# SMP_ASCII.net
KiCad netlist of a schematic drawn in Altium Designer
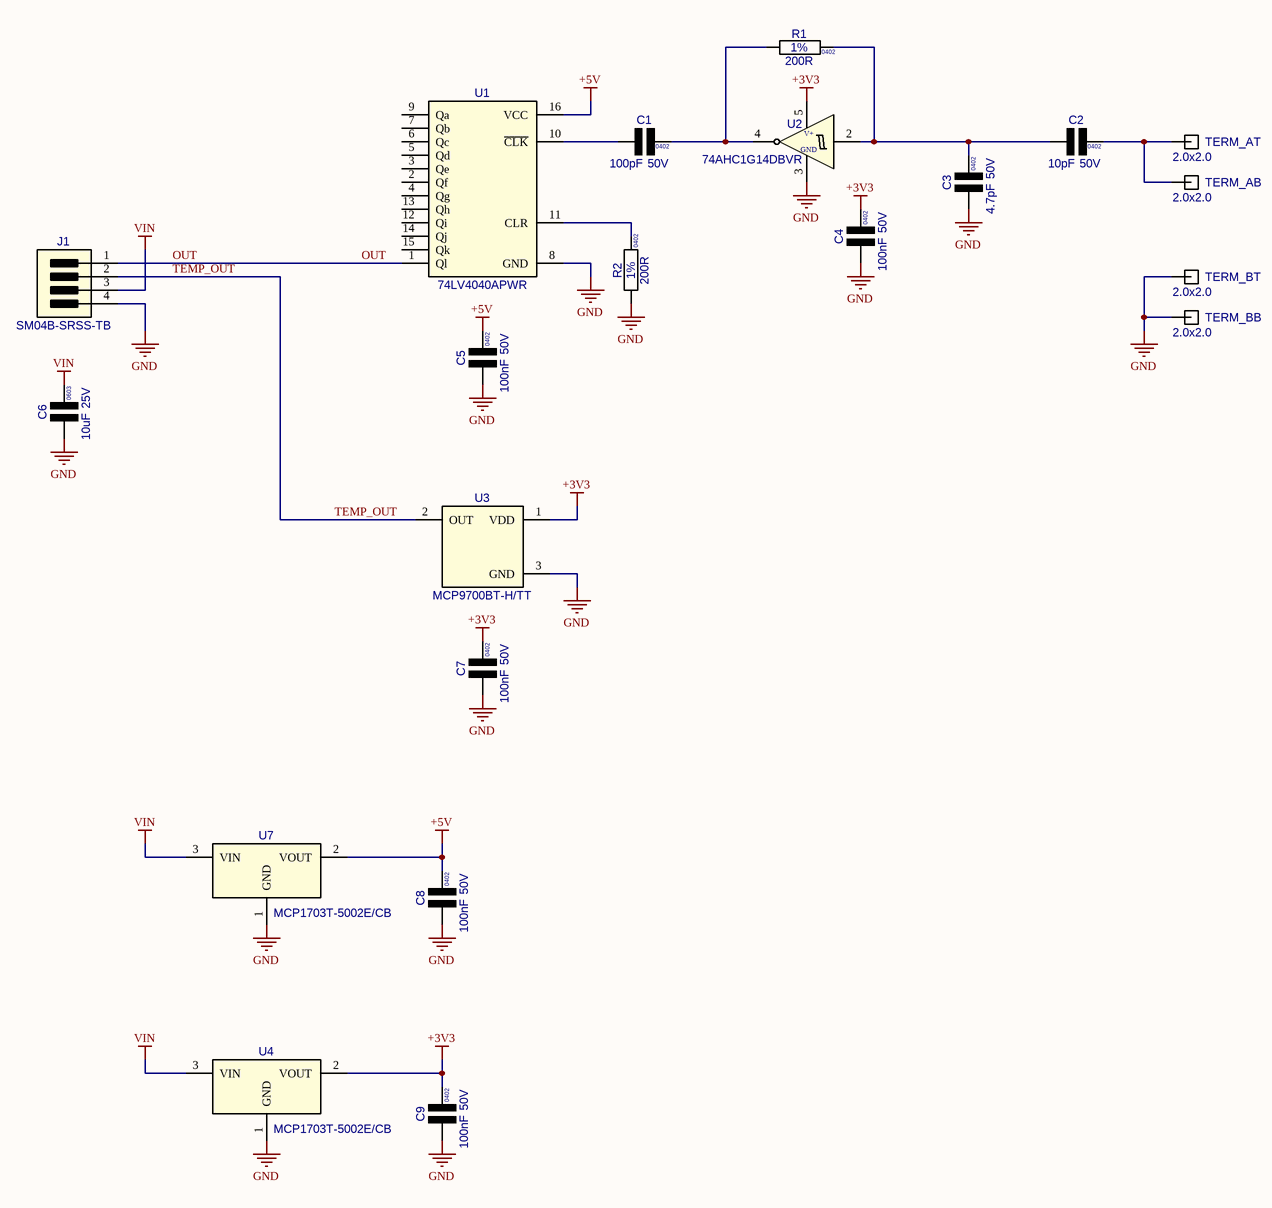
[diagram p0: SMP ASCII.SchDoc]

(export (version "E")
  (design (tool "Eeschema 10.0.6"))
  (components
    (comp (ref "C1")
      (value "100pF")
      (footprint "CAPC0402X60N")
      (description "Cap Ceramic C0G/NP0")
      (fields
        (field (name "MANUFACTURER") "Various")
        (field (name "PART NUMBER") "100pF 0402 50V 10% C0G/NP0")
        (field (name "VOLTAGE") "50V")
        (field (name "TEXT1") "0402")
      )
      (libsource (lib "Cap-Cer-SMD_V2") (part "100pF_0402N_50V_10%_C0G/NP0"))
    )
    (comp (ref "C2")
      (value "10pF")
      (footprint "CAPC0402X60N")
      (description "Cap Ceramic C0G/NP0")
      (fields
        (field (name "MANUFACTURER") "Various")
        (field (name "PART NUMBER") "10pF 0402 50V 5% C0G/NP0")
        (field (name "VOLTAGE") "50V")
        (field (name "TEXT1") "0402")
      )
      (libsource (lib "Cap-Cer-SMD_V2") (part "10pF_0402N_50V_5%_C0G/NP0"))
    )
    (comp (ref "C3")
      (value "4.7pF")
      (footprint "CAPC0402X60N")
      (description "Cap Ceramic C0G/NP0")
      (fields
        (field (name "MANUFACTURER") "Various")
        (field (name "PART NUMBER") "4.7pF 0402 50V 5% C0G/NP0")
        (field (name "VOLTAGE") "50V")
        (field (name "TEXT1") "0402")
      )
      (libsource (lib "Cap-Cer-SMD_V2") (part "4.7pF_0402N_50V_5%_C0G/NP0"))
    )
    (comp (ref "C4")
      (value "100nF")
      (footprint "CAPC0402X60N")
      (description "Cap Ceramic X5R")
      (fields
        (field (name "MANUFACTURER") "Various")
        (field (name "PART NUMBER") "100nF 0402 50V 5% X5R")
        (field (name "VOLTAGE") "50V")
        (field (name "TEXT1") "0402")
      )
      (libsource (lib "Cap-Cer-SMD_V2") (part "100nF_0402N_50V_5%_X5R"))
    )
    (comp (ref "C5")
      (value "100nF")
      (footprint "CAPC0402X60N")
      (description "Cap Ceramic X5R")
      (fields
        (field (name "MANUFACTURER") "Various")
        (field (name "PART NUMBER") "100nF 0402 50V 5% X5R")
        (field (name "VOLTAGE") "50V")
        (field (name "TEXT1") "0402")
      )
      (libsource (lib "Cap-Cer-SMD_V2") (part "100nF_0402N_50V_5%_X5R"))
    )
    (comp (ref "C6")
      (value "10uF")
      (footprint "CAPC0603X85N")
      (description "Cap Ceramic X5R")
      (fields
        (field (name "MANUFACTURER") "Various")
        (field (name "PART NUMBER") "10uF 0603 25V 10% X5R")
        (field (name "VOLTAGE") "25V")
        (field (name "TEXT1") "0603")
      )
      (libsource (lib "Cap-Cer-SMD_V2") (part "10uF_0603N_25V_10%_X5R"))
    )
    (comp (ref "C7")
      (value "100nF")
      (footprint "CAPC0402X60N")
      (description "Cap Ceramic X5R")
      (fields
        (field (name "MANUFACTURER") "Various")
        (field (name "PART NUMBER") "100nF 0402 50V 5% X5R")
        (field (name "VOLTAGE") "50V")
        (field (name "TEXT1") "0402")
      )
      (libsource (lib "Cap-Cer-SMD_V2") (part "100nF_0402N_50V_5%_X5R"))
    )
    (comp (ref "C8")
      (value "100nF")
      (footprint "CAPC0402X60N")
      (description "Cap Ceramic X5R")
      (fields
        (field (name "MANUFACTURER") "Various")
        (field (name "PART NUMBER") "100nF 0402 50V 5% X5R")
        (field (name "VOLTAGE") "50V")
        (field (name "TEXT1") "0402")
      )
      (libsource (lib "Cap-Cer-SMD_V2") (part "100nF_0402N_50V_5%_X5R"))
    )
    (comp (ref "C9")
      (value "100nF")
      (footprint "CAPC0402X60N")
      (description "Cap Ceramic X5R")
      (fields
        (field (name "MANUFACTURER") "Various")
        (field (name "PART NUMBER") "100nF 0402 50V 5% X5R")
        (field (name "VOLTAGE") "50V")
        (field (name "TEXT1") "0402")
      )
      (libsource (lib "Cap-Cer-SMD_V2") (part "100nF_0402N_50V_5%_X5R"))
    )
    (comp (ref "J1")
      (value "SM04B-SRSS-TB")
      (footprint "SM04B-SRSS-TB")
      (description "Connector Wire to Board 1.0mm Rt Angle")
      (fields (field (name "MANUFACTURER") "JST"))
      (libsource (lib "Connector-WtB") (part "SM04B-SRSS-TB"))
    )
    (comp (ref "R1")
      (value "200R")
      (footprint "RESC0402X40N")
      (description "Resistor Chip SMD")
      (fields
        (field (name "MANUFACTURER") "Various")
        (field (name "PART NUMBER") "200R 0402 1%")
        (field (name "TOL") "1%")
        (field (name "TEXT1") "0402")
      )
      (libsource (lib "Res-SMD_V2") (part "200R_0402"))
    )
    (comp (ref "R2")
      (value "200R")
      (footprint "RESC0402X40N")
      (description "Resistor Chip SMD")
      (fields
        (field (name "MANUFACTURER") "Various")
        (field (name "PART NUMBER") "200R 0402 1%")
        (field (name "TOL") "1%")
        (field (name "TEXT1") "0402")
      )
      (libsource (lib "Res-SMD_V2") (part "200R_0402"))
    )
    (comp (ref "TERM_AB")
      (value "Pad-SMD-2.0x2.0mm-H_Rectangle")
      (footprint "PAD-SMD-2.0x2.0mm Rect")
      (description "Surface Mount Pad 2.0x2.0mm Rectangle")
      (fields (field (name "MANUFACTURER") "NA") (field (name "PART NUMBER") "2.0x2.0"))
      (libsource (lib "Mechanical_V2") (part "Pad-SMD-2.0x2.0mm_Rectangle"))
    )
    (comp (ref "TERM_AT")
      (value "Pad-SMD-2.0x2.0mm-H_Rectangle")
      (footprint "PAD-SMD-2.0x2.0mm Rect")
      (description "Surface Mount Pad 2.0x2.0mm Rectangle")
      (fields (field (name "MANUFACTURER") "NA") (field (name "PART NUMBER") "2.0x2.0"))
      (libsource (lib "Mechanical_V2") (part "Pad-SMD-2.0x2.0mm_Rectangle"))
    )
    (comp (ref "TERM_BB")
      (value "Pad-SMD-2.0x2.0mm-H_Rectangle")
      (footprint "PAD-SMD-2.0x2.0mm Rect")
      (description "Surface Mount Pad 2.0x2.0mm Rectangle")
      (fields (field (name "MANUFACTURER") "NA") (field (name "PART NUMBER") "2.0x2.0"))
      (libsource (lib "Mechanical_V2") (part "Pad-SMD-2.0x2.0mm_Rectangle"))
    )
    (comp (ref "TERM_BT")
      (value "Pad-SMD-2.0x2.0mm-H_Rectangle")
      (footprint "PAD-SMD-2.0x2.0mm Rect")
      (description "Surface Mount Pad 2.0x2.0mm Rectangle")
      (fields (field (name "MANUFACTURER") "NA") (field (name "PART NUMBER") "2.0x2.0"))
      (libsource (lib "Mechanical_V2") (part "Pad-SMD-2.0x2.0mm_Rectangle"))
    )
    (comp (ref "U1")
      (value "74LV4040APWR")
      (footprint "TSSOP16-4.5x5.0")
      (description "IC 12-Bit Binary Ripple Counter")
      (fields (field (name "MANUFACTURER") "Texas") (field (name "PART NUMBER") "74LV4040APWR"))
      (libsource (lib "IC-CMOS") (part "74LV4040APWR_TSSOP16"))
    )
    (comp (ref "U2")
      (value "74AHC1G14DBVR")
      (footprint "SOT23-5")
      (description "IC Single Schmitt-Trigger Inverter")
      (fields (field (name "MANUFACTURER") "Texas") (field (name "PART NUMBER") "74AHC1G14DBVR"))
      (libsource (lib "IC-TTL") (part "74AHC1G14DBVR_SOT23-5"))
    )
    (comp (ref "U3")
      (value "MCP9700BT-H/TT")
      (footprint "SOT23")
      (description "IC Temperature Sensor -40 to 150 C")
      (fields (field (name "MANUFACTURER") "Microchip") (field (name "PART NUMBER") "MCP9700BT-H/TT"))
      (libsource (lib "IC-Sensors") (part "MCP9700BT-H/TT-SOT23"))
    )
    (comp (ref "U4")
      (value "MCP1703T-5002E/CB")
      (footprint "SOT23A")
      (description "Voltage Regulator LDO 250mA")
      (fields (field (name "MANUFACTURER") "Microchip") (field (name "PART NUMBER") "MCP1703T-5002E/CB"))
      (libsource (lib "IC-Regulator") (part "MCP1703T-5002E/CB_SOT23A"))
    )
    (comp (ref "U7")
      (value "MCP1703T-5002E/CB")
      (footprint "SOT23A")
      (description "Voltage Regulator LDO 250mA")
      (fields (field (name "MANUFACTURER") "Microchip") (field (name "PART NUMBER") "MCP1703T-5002E/CB"))
      (libsource (lib "IC-Regulator") (part "MCP1703T-5002E/CB_SOT23A"))
    )
  )
  (nets
    (net (code "1") (name "+3V3") (class "Default")
      (node (ref "C4") (pin "1") (pinfunction "1_1") (pintype "passive"))
      (node (ref "C7") (pin "1") (pinfunction "1_1") (pintype "passive"))
      (node (ref "C9") (pin "1") (pinfunction "1_1") (pintype "passive"))
      (node (ref "U2") (pin "5") (pinfunction "V+_5") (pintype "power_in"))
      (node (ref "U3") (pin "1") (pinfunction "VDD_1") (pintype "passive"))
      (node (ref "U4") (pin "2") (pinfunction "VOUT_2") (pintype "passive"))
    )
    (net (code "2") (name "+5V") (class "Default")
      (node (ref "C5") (pin "1") (pinfunction "1_1") (pintype "passive"))
      (node (ref "C8") (pin "1") (pinfunction "1_1") (pintype "passive"))
      (node (ref "U1") (pin "16") (pinfunction "VCC_16") (pintype "passive"))
      (node (ref "U7") (pin "2") (pinfunction "VOUT_2") (pintype "passive"))
    )
    (net (code "3") (name "/OUT") (class "Default")
      (node (ref "J1") (pin "1") (pinfunction "1_1") (pintype "passive"))
      (node (ref "U1") (pin "1") (pinfunction "Ql_1") (pintype "passive"))
    )
    (net (code "4") (name "/TEMP_OUT") (class "Default")
      (node (ref "J1") (pin "2") (pinfunction "2_2") (pintype "passive"))
      (node (ref "U3") (pin "2") (pinfunction "OUT_2") (pintype "passive"))
    )
    (net (code "5") (name "GND") (class "Default")
      (node (ref "C3") (pin "2") (pinfunction "2_2") (pintype "passive"))
      (node (ref "C4") (pin "2") (pinfunction "2_2") (pintype "passive"))
      (node (ref "C5") (pin "2") (pinfunction "2_2") (pintype "passive"))
      (node (ref "C6") (pin "2") (pinfunction "2_2") (pintype "passive"))
      (node (ref "C7") (pin "2") (pinfunction "2_2") (pintype "passive"))
      (node (ref "C8") (pin "2") (pinfunction "2_2") (pintype "passive"))
      (node (ref "C9") (pin "2") (pinfunction "2_2") (pintype "passive"))
      (node (ref "J1") (pin "4") (pinfunction "4_4") (pintype "passive"))
      (node (ref "R2") (pin "1") (pinfunction "1_1") (pintype "passive"))
      (node (ref "TERM_BB") (pin "1") (pinfunction "1_1") (pintype "passive"))
      (node (ref "TERM_BT") (pin "1") (pinfunction "1_1") (pintype "passive"))
      (node (ref "U1") (pin "8") (pinfunction "GND_8") (pintype "passive"))
      (node (ref "U2") (pin "3") (pinfunction "GND_3") (pintype "power_in"))
      (node (ref "U3") (pin "3") (pinfunction "GND_3") (pintype "power_in"))
      (node (ref "U4") (pin "1") (pinfunction "GND_1") (pintype "power_in"))
      (node (ref "U7") (pin "1") (pinfunction "GND_1") (pintype "power_in"))
    )
    (net (code "6") (name "Net-(C2-Pad1)") (class "Default")
      (node (ref "C2") (pin "1") (pinfunction "1_1") (pintype "passive"))
      (node (ref "TERM_AB") (pin "1") (pinfunction "1_1") (pintype "passive"))
      (node (ref "TERM_AT") (pin "1") (pinfunction "1_1") (pintype "passive"))
    )
    (net (code "7") (name "Net-(U1-CLK)") (class "Default")
      (node (ref "C1") (pin "2") (pinfunction "2_2") (pintype "passive"))
      (node (ref "U1") (pin "10") (pinfunction "CLK_10") (pintype "passive"))
    )
    (net (code "8") (name "Net-(U1-CLR)") (class "Default")
      (node (ref "R2") (pin "2") (pinfunction "2_2") (pintype "passive"))
      (node (ref "U1") (pin "11") (pinfunction "CLR_11") (pintype "passive"))
    )
    (net (code "9") (name "Net-(U2-A)") (class "Default")
      (node (ref "C2") (pin "2") (pinfunction "2_2") (pintype "passive"))
      (node (ref "C3") (pin "1") (pinfunction "1_1") (pintype "passive"))
      (node (ref "R1") (pin "2") (pinfunction "2_2") (pintype "passive"))
      (node (ref "U2") (pin "2") (pinfunction "A_2") (pintype "passive"))
    )
    (net (code "10") (name "Net-(U2-Y)") (class "Default")
      (node (ref "C1") (pin "1") (pinfunction "1_1") (pintype "passive"))
      (node (ref "R1") (pin "1") (pinfunction "1_1") (pintype "passive"))
      (node (ref "U2") (pin "4") (pinfunction "Y_4") (pintype "passive"))
    )
    (net (code "11") (name "VIN") (class "Default")
      (node (ref "C6") (pin "1") (pinfunction "1_1") (pintype "passive"))
      (node (ref "J1") (pin "3") (pinfunction "3_3") (pintype "passive"))
      (node (ref "U4") (pin "3") (pinfunction "VIN_3") (pintype "passive"))
      (node (ref "U7") (pin "3") (pinfunction "VIN_3") (pintype "passive"))
    )
    (net (code "12") (name "unconnected-(U1-Qa-Pad9)") (class "Default")
      (node (ref "U1") (pin "9") (pinfunction "Qa_9") (pintype "passive"))
    )
    (net (code "13") (name "unconnected-(U1-Qb-Pad7)") (class "Default")
      (node (ref "U1") (pin "7") (pinfunction "Qb_7") (pintype "passive"))
    )
    (net (code "14") (name "unconnected-(U1-Qc-Pad6)") (class "Default")
      (node (ref "U1") (pin "6") (pinfunction "Qc_6") (pintype "passive"))
    )
    (net (code "15") (name "unconnected-(U1-Qd-Pad5)") (class "Default")
      (node (ref "U1") (pin "5") (pinfunction "Qd_5") (pintype "passive"))
    )
    (net (code "16") (name "unconnected-(U1-Qe-Pad3)") (class "Default")
      (node (ref "U1") (pin "3") (pinfunction "Qe_3") (pintype "passive"))
    )
    (net (code "17") (name "unconnected-(U1-Qf-Pad2)") (class "Default")
      (node (ref "U1") (pin "2") (pinfunction "Qf_2") (pintype "passive"))
    )
    (net (code "18") (name "unconnected-(U1-Qg-Pad4)") (class "Default")
      (node (ref "U1") (pin "4") (pinfunction "Qg_4") (pintype "passive"))
    )
    (net (code "19") (name "unconnected-(U1-Qh-Pad13)") (class "Default")
      (node (ref "U1") (pin "13") (pinfunction "Qh_13") (pintype "passive"))
    )
    (net (code "20") (name "unconnected-(U1-Qi-Pad12)") (class "Default")
      (node (ref "U1") (pin "12") (pinfunction "Qi_12") (pintype "passive"))
    )
    (net (code "21") (name "unconnected-(U1-Qj-Pad14)") (class "Default")
      (node (ref "U1") (pin "14") (pinfunction "Qj_14") (pintype "passive"))
    )
    (net (code "22") (name "unconnected-(U1-Qk-Pad15)") (class "Default")
      (node (ref "U1") (pin "15") (pinfunction "Qk_15") (pintype "passive"))
    )
    (net (code "23") (name "unconnected-(U2-NC-Pad1)") (class "Default")
      (node (ref "U2") (pin "1") (pinfunction "NC_1") (pintype "passive"))
    )
  )
)
